# M_F_ext_breadboard.net
KiCad netlist of a schematic drawn in EAGLE
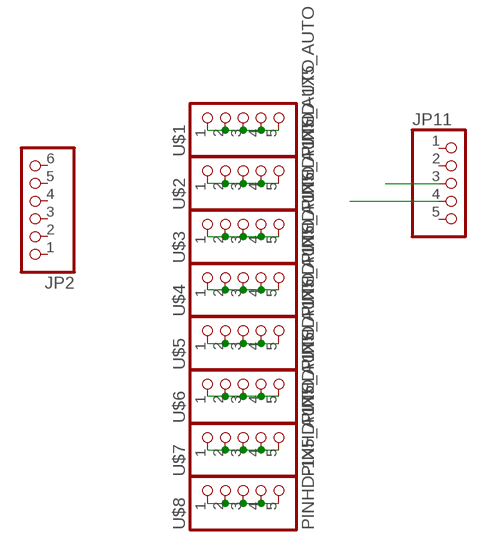
[diagram p0: schematic, sheet 1]

(export (version "E")
  (design (tool "Eeschema 10.0.6"))
  (components
    (comp (ref "JP2")
      (value "PINHD-1X6")
      (footprint "eagle-import:1X06")
      (libsource (lib "eagle-import") (part "PINHD-1X6"))
    )
    (comp (ref "JP11")
      (value "PINHD-1X5")
      (footprint "eagle-import:1X05")
      (libsource (lib "eagle-import") (part "PINHD-1X5"))
    )
    (comp (ref "U$1")
      (value "PINHD-1X5_AUTO")
      (footprint "eagle-import:1X5_AUTO")
      (libsource (lib "eagle-import") (part "PINHD-1X5_AUTO"))
    )
    (comp (ref "U$2")
      (value "PINHD-1X5_AUTO")
      (footprint "eagle-import:1X5_AUTO")
      (libsource (lib "eagle-import") (part "PINHD-1X5_AUTO"))
    )
    (comp (ref "U$3")
      (value "PINHD-1X5_AUTO")
      (footprint "eagle-import:1X5_AUTO")
      (libsource (lib "eagle-import") (part "PINHD-1X5_AUTO"))
    )
    (comp (ref "U$4")
      (value "PINHD-1X5_AUTO")
      (footprint "eagle-import:1X5_AUTO")
      (libsource (lib "eagle-import") (part "PINHD-1X5_AUTO"))
    )
    (comp (ref "U$5")
      (value "PINHD-1X5_AUTO")
      (footprint "eagle-import:1X5_AUTO")
      (libsource (lib "eagle-import") (part "PINHD-1X5_AUTO"))
    )
    (comp (ref "U$6")
      (value "PINHD-1X5_AUTO")
      (footprint "eagle-import:1X5_AUTO")
      (libsource (lib "eagle-import") (part "PINHD-1X5_AUTO"))
    )
    (comp (ref "U$7")
      (value "PINHD-1X5_AUTO")
      (footprint "eagle-import:1X5_AUTO")
      (libsource (lib "eagle-import") (part "PINHD-1X5_AUTO"))
    )
    (comp (ref "U$8")
      (value "PINHD-1X5_AUTO")
      (footprint "eagle-import:1X5_AUTO")
      (libsource (lib "eagle-import") (part "PINHD-1X5_AUTO"))
    )
  )
  (nets
    (net (code "1") (name "Net-(U$1-Pad1)") (class "Default")
      (node (ref "U$1") (pin "1") (pinfunction "1_1") (pintype "passive"))
      (node (ref "U$1") (pin "2") (pinfunction "2_2") (pintype "passive"))
      (node (ref "U$1") (pin "3") (pinfunction "3_3") (pintype "passive"))
      (node (ref "U$1") (pin "4") (pinfunction "4_4") (pintype "passive"))
      (node (ref "U$1") (pin "5") (pinfunction "5_5") (pintype "passive"))
    )
    (net (code "2") (name "Net-(U$2-Pad1)") (class "Default")
      (node (ref "U$2") (pin "1") (pinfunction "1_1") (pintype "passive"))
      (node (ref "U$2") (pin "2") (pinfunction "2_2") (pintype "passive"))
      (node (ref "U$2") (pin "3") (pinfunction "3_3") (pintype "passive"))
      (node (ref "U$2") (pin "4") (pinfunction "4_4") (pintype "passive"))
      (node (ref "U$2") (pin "5") (pinfunction "5_5") (pintype "passive"))
    )
    (net (code "3") (name "Net-(U$3-Pad1)") (class "Default")
      (node (ref "U$3") (pin "1") (pinfunction "1_1") (pintype "passive"))
      (node (ref "U$3") (pin "2") (pinfunction "2_2") (pintype "passive"))
      (node (ref "U$3") (pin "3") (pinfunction "3_3") (pintype "passive"))
      (node (ref "U$3") (pin "4") (pinfunction "4_4") (pintype "passive"))
      (node (ref "U$3") (pin "5") (pinfunction "5_5") (pintype "passive"))
    )
    (net (code "4") (name "Net-(U$4-Pad1)") (class "Default")
      (node (ref "U$4") (pin "1") (pinfunction "1_1") (pintype "passive"))
      (node (ref "U$4") (pin "2") (pinfunction "2_2") (pintype "passive"))
      (node (ref "U$4") (pin "3") (pinfunction "3_3") (pintype "passive"))
      (node (ref "U$4") (pin "4") (pinfunction "4_4") (pintype "passive"))
      (node (ref "U$4") (pin "5") (pinfunction "5_5") (pintype "passive"))
    )
    (net (code "5") (name "Net-(U$5-Pad1)") (class "Default")
      (node (ref "U$5") (pin "1") (pinfunction "1_1") (pintype "passive"))
      (node (ref "U$5") (pin "2") (pinfunction "2_2") (pintype "passive"))
      (node (ref "U$5") (pin "3") (pinfunction "3_3") (pintype "passive"))
      (node (ref "U$5") (pin "4") (pinfunction "4_4") (pintype "passive"))
      (node (ref "U$5") (pin "5") (pinfunction "5_5") (pintype "passive"))
    )
    (net (code "6") (name "Net-(U$6-Pad1)") (class "Default")
      (node (ref "U$6") (pin "1") (pinfunction "1_1") (pintype "passive"))
      (node (ref "U$6") (pin "2") (pinfunction "2_2") (pintype "passive"))
      (node (ref "U$6") (pin "3") (pinfunction "3_3") (pintype "passive"))
      (node (ref "U$6") (pin "4") (pinfunction "4_4") (pintype "passive"))
      (node (ref "U$6") (pin "5") (pinfunction "5_5") (pintype "passive"))
    )
    (net (code "7") (name "Net-(U$7-Pad1)") (class "Default")
      (node (ref "U$7") (pin "1") (pinfunction "1_1") (pintype "passive"))
      (node (ref "U$7") (pin "2") (pinfunction "2_2") (pintype "passive"))
      (node (ref "U$7") (pin "3") (pinfunction "3_3") (pintype "passive"))
      (node (ref "U$7") (pin "4") (pinfunction "4_4") (pintype "passive"))
      (node (ref "U$7") (pin "5") (pinfunction "5_5") (pintype "passive"))
    )
    (net (code "8") (name "Net-(U$8-Pad1)") (class "Default")
      (node (ref "U$8") (pin "1") (pinfunction "1_1") (pintype "passive"))
      (node (ref "U$8") (pin "2") (pinfunction "2_2") (pintype "passive"))
      (node (ref "U$8") (pin "3") (pinfunction "3_3") (pintype "passive"))
      (node (ref "U$8") (pin "4") (pinfunction "4_4") (pintype "passive"))
      (node (ref "U$8") (pin "5") (pinfunction "5_5") (pintype "passive"))
    )
    (net (code "9") (name "unconnected-(JP2-Pad1)") (class "Default")
      (node (ref "JP2") (pin "1") (pinfunction "1_1") (pintype "passive"))
    )
    (net (code "10") (name "unconnected-(JP2-Pad2)") (class "Default")
      (node (ref "JP2") (pin "2") (pinfunction "2_2") (pintype "passive"))
    )
    (net (code "11") (name "unconnected-(JP2-Pad3)") (class "Default")
      (node (ref "JP2") (pin "3") (pinfunction "3_3") (pintype "passive"))
    )
    (net (code "12") (name "unconnected-(JP2-Pad4)") (class "Default")
      (node (ref "JP2") (pin "4") (pinfunction "4_4") (pintype "passive"))
    )
    (net (code "13") (name "unconnected-(JP2-Pad5)") (class "Default")
      (node (ref "JP2") (pin "5") (pinfunction "5_5") (pintype "passive"))
    )
    (net (code "14") (name "unconnected-(JP2-Pad6)") (class "Default")
      (node (ref "JP2") (pin "6") (pinfunction "6_6") (pintype "passive"))
    )
    (net (code "15") (name "unconnected-(JP11-Pad1)") (class "Default")
      (node (ref "JP11") (pin "1") (pinfunction "1_1") (pintype "passive"))
    )
    (net (code "16") (name "unconnected-(JP11-Pad2)") (class "Default")
      (node (ref "JP11") (pin "2") (pinfunction "2_2") (pintype "passive"))
    )
    (net (code "17") (name "unconnected-(JP11-Pad3)") (class "Default")
      (node (ref "JP11") (pin "3") (pinfunction "3_3") (pintype "passive"))
    )
    (net (code "18") (name "unconnected-(JP11-Pad4)") (class "Default")
      (node (ref "JP11") (pin "4") (pinfunction "4_4") (pintype "passive"))
    )
    (net (code "19") (name "unconnected-(JP11-Pad5)") (class "Default")
      (node (ref "JP11") (pin "5") (pinfunction "5_5") (pintype "passive"))
    )
  )
)
